# tri_to_ramp-pls_2-25-23.net
KiCad netlist of a schematic drawn in EAGLE
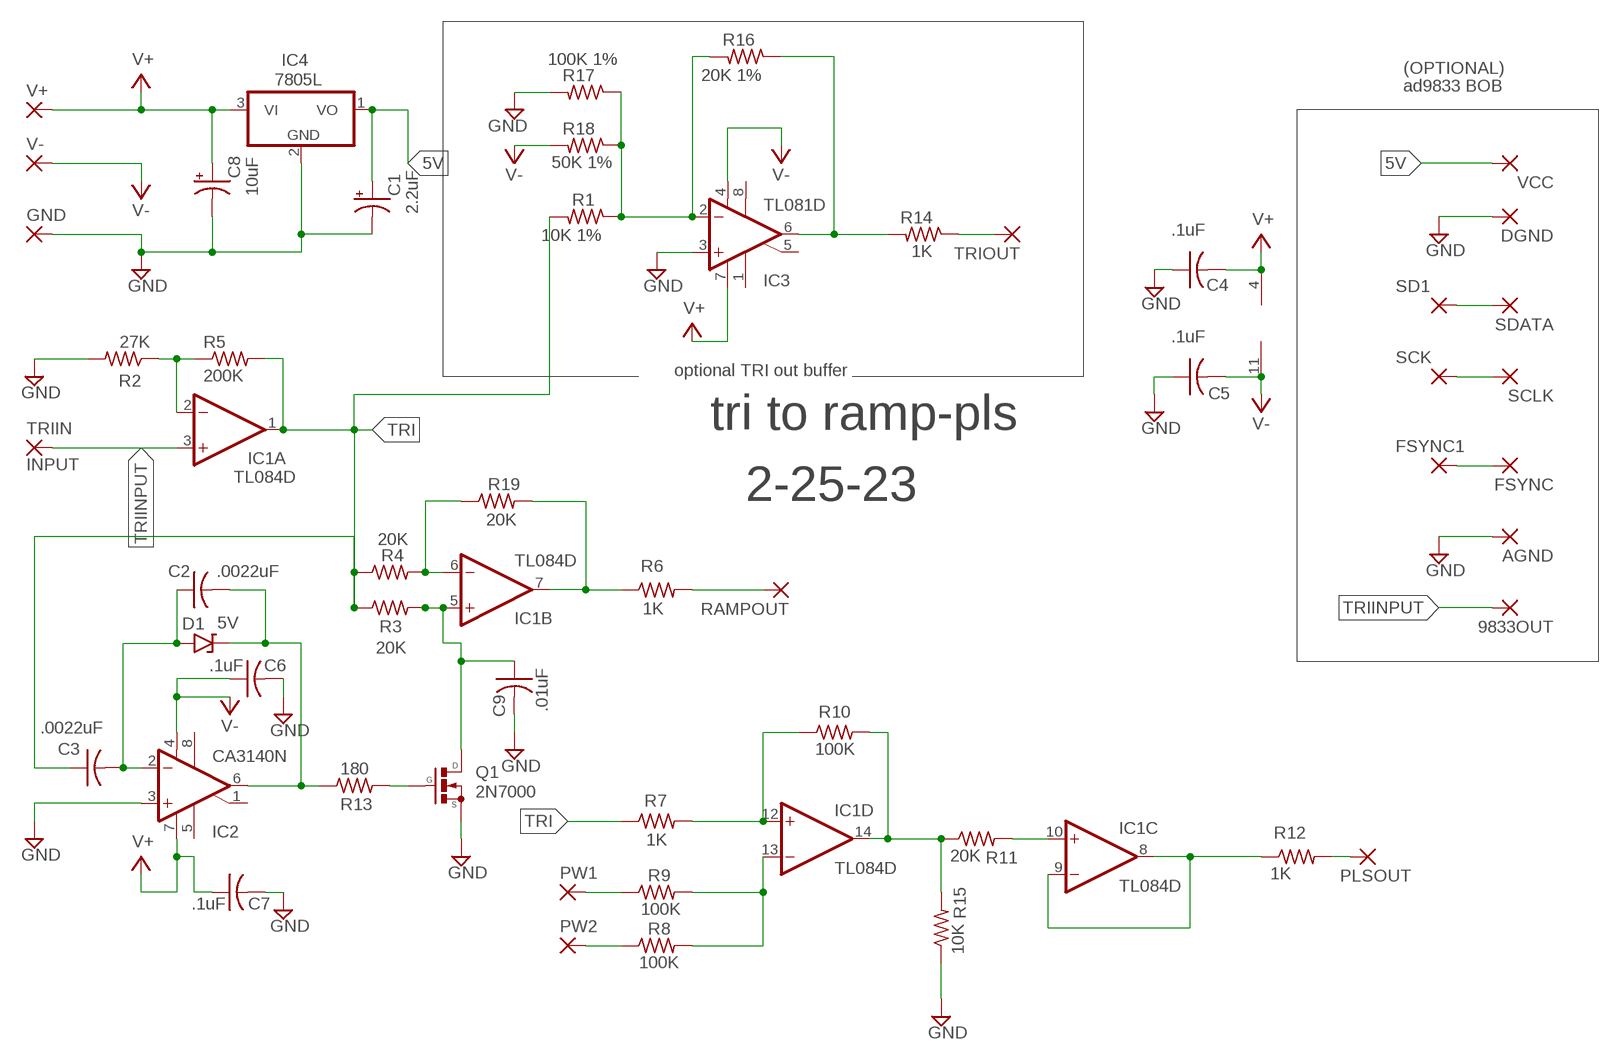
[diagram p0: schematic, sheet 1]

(export (version "E")
  (design (tool "Eeschema 10.0.6"))
  (components
    (comp (ref "9833OUT")
      (value "WIREPAD1,6/0,8")
      (footprint "eagle-import:1,6_0,8")
      (libsource (lib "eagle-import") (part "WIREPAD1,6/0,8"))
    )
    (comp (ref "AGND")
      (value "WIREPAD1,6/0,8")
      (footprint "eagle-import:1,6_0,8")
      (libsource (lib "eagle-import") (part "WIREPAD1,6/0,8"))
    )
    (comp (ref "C1")
      (value "2.2uF")
      (footprint "eagle-import:E5-4")
      (libsource (lib "eagle-import") (part "CPOL-USE5-4"))
    )
    (comp (ref "C2")
      (value ".0022uF")
      (footprint "eagle-import:C050-030X075")
      (libsource (lib "eagle-import") (part "C-US050-030X075"))
    )
    (comp (ref "C3")
      (value ".0022uF")
      (footprint "eagle-import:C050-035X075")
      (libsource (lib "eagle-import") (part "C-US050-035X075"))
    )
    (comp (ref "C4")
      (value ".1uF")
      (footprint "eagle-import:C025-025X050")
      (libsource (lib "eagle-import") (part "C-US025-025X050"))
    )
    (comp (ref "C5")
      (value ".1uF")
      (footprint "eagle-import:C025-025X050")
      (libsource (lib "eagle-import") (part "C-US025-025X050"))
    )
    (comp (ref "C6")
      (value ".1uF")
      (footprint "eagle-import:C025-025X050")
      (libsource (lib "eagle-import") (part "C-US025-025X050"))
    )
    (comp (ref "C7")
      (value ".1uF")
      (footprint "eagle-import:C025-025X050")
      (libsource (lib "eagle-import") (part "C-US025-025X050"))
    )
    (comp (ref "C8")
      (value "10uF")
      (footprint "eagle-import:E5-4")
      (libsource (lib "eagle-import") (part "CPOL-USE5-4"))
    )
    (comp (ref "C9")
      (value ".01uF")
      (footprint "eagle-import:C050-035X075")
      (libsource (lib "eagle-import") (part "C-US050-035X075"))
    )
    (comp (ref "D1")
      (value "5V")
      (footprint "eagle-import:DO41-3")
      (libsource (lib "eagle-import") (part "ZENER.3"))
    )
    (comp (ref "DGND")
      (value "WIREPAD1,6/0,8")
      (footprint "eagle-import:1,6_0,8")
      (libsource (lib "eagle-import") (part "WIREPAD1,6/0,8"))
    )
    (comp (ref "FSYNC")
      (value "WIREPAD1,6/0,8")
      (footprint "eagle-import:1,6_0,8")
      (libsource (lib "eagle-import") (part "WIREPAD1,6/0,8"))
    )
    (comp (ref "FSYNC1")
      (value "WIREPAD1,6/0,8")
      (footprint "eagle-import:1,6_0,8")
      (libsource (lib "eagle-import") (part "WIREPAD1,6/0,8"))
    )
    (comp (ref "GND")
      (value "WIREPAD1,6/0,8")
      (footprint "eagle-import:1,6_0,8")
      (libsource (lib "eagle-import") (part "WIREPAD1,6/0,8"))
    )
    (comp (ref "IC1")
      (value "TL084D")
      (footprint "eagle-import:SO14")
      (libsource (lib "eagle-import") (part "TL084D"))
    )
    (comp (ref "IC2")
      (value "CA3140N")
      (footprint "eagle-import:DIL08")
      (libsource (lib "eagle-import") (part "CA3140N"))
    )
    (comp (ref "IC3")
      (value "TL081D")
      (footprint "eagle-import:SO08")
      (libsource (lib "eagle-import") (part "TL081D"))
    )
    (comp (ref "IC4")
      (value "7805L")
      (footprint "eagle-import:ADAFRUIT_TO92")
      (libsource (lib "eagle-import") (part "ADAFRUIT_78L05"))
    )
    (comp (ref "PLSOUT")
      (value "WIREPAD1,6/0,8")
      (footprint "eagle-import:1,6_0,8")
      (libsource (lib "eagle-import") (part "WIREPAD1,6/0,8"))
    )
    (comp (ref "PW1")
      (value "WIREPAD1,6/0,8")
      (footprint "eagle-import:1,6_0,8")
      (libsource (lib "eagle-import") (part "WIREPAD1,6/0,8"))
    )
    (comp (ref "PW2")
      (value "WIREPAD1,6/0,8")
      (footprint "eagle-import:1,6_0,8")
      (libsource (lib "eagle-import") (part "WIREPAD1,6/0,8"))
    )
    (comp (ref "Q1")
      (value "2N7000")
      (footprint "eagle-import:TO92-")
      (libsource (lib "eagle-import") (part "2N7000"))
    )
    (comp (ref "R1")
      (value "10K 1%")
      (footprint "eagle-import:0204_7")
      (libsource (lib "eagle-import") (part "R-US_0204/7"))
    )
    (comp (ref "R2")
      (value "27K")
      (footprint "eagle-import:0204_7")
      (libsource (lib "eagle-import") (part "R-US_0204/7"))
    )
    (comp (ref "R3")
      (value "20K")
      (footprint "eagle-import:0204_7")
      (libsource (lib "eagle-import") (part "R-US_0204/7"))
    )
    (comp (ref "R4")
      (value "20K")
      (footprint "eagle-import:0204_7")
      (libsource (lib "eagle-import") (part "R-US_0204/7"))
    )
    (comp (ref "R5")
      (value "200K")
      (footprint "eagle-import:0204_7")
      (libsource (lib "eagle-import") (part "R-US_0204/7"))
    )
    (comp (ref "R6")
      (value "1K")
      (footprint "eagle-import:0204_7")
      (libsource (lib "eagle-import") (part "R-US_0204/7"))
    )
    (comp (ref "R7")
      (value "1K")
      (footprint "eagle-import:0204_7")
      (libsource (lib "eagle-import") (part "R-US_0204/7"))
    )
    (comp (ref "R8")
      (value "100K")
      (footprint "eagle-import:0204_7")
      (libsource (lib "eagle-import") (part "R-US_0204/7"))
    )
    (comp (ref "R9")
      (value "100K")
      (footprint "eagle-import:0204_7")
      (libsource (lib "eagle-import") (part "R-US_0204/7"))
    )
    (comp (ref "R10")
      (value "100K")
      (footprint "eagle-import:0204_7")
      (libsource (lib "eagle-import") (part "R-US_0204/7"))
    )
    (comp (ref "R11")
      (value "20K")
      (footprint "eagle-import:0204_7")
      (libsource (lib "eagle-import") (part "R-US_0204/7"))
    )
    (comp (ref "R12")
      (value "1K")
      (footprint "eagle-import:0204_7")
      (libsource (lib "eagle-import") (part "R-US_0204/7"))
    )
    (comp (ref "R13")
      (value "180")
      (footprint "eagle-import:0204_7")
      (libsource (lib "eagle-import") (part "R-US_0204/7"))
    )
    (comp (ref "R14")
      (value "1K")
      (footprint "eagle-import:0204_7")
      (libsource (lib "eagle-import") (part "R-US_0204/7"))
    )
    (comp (ref "R15")
      (value "10K")
      (footprint "eagle-import:0204_7")
      (libsource (lib "eagle-import") (part "R-US_0204/7"))
    )
    (comp (ref "R16")
      (value "20K 1%")
      (footprint "eagle-import:0204_7")
      (libsource (lib "eagle-import") (part "R-US_0204/7"))
    )
    (comp (ref "R17")
      (value "100K 1%")
      (footprint "eagle-import:0204_7")
      (libsource (lib "eagle-import") (part "R-US_0204/7"))
    )
    (comp (ref "R18")
      (value "50K 1%")
      (footprint "eagle-import:0204_7")
      (libsource (lib "eagle-import") (part "R-US_0204/7"))
    )
    (comp (ref "R19")
      (value "20K")
      (footprint "eagle-import:0204_7")
      (libsource (lib "eagle-import") (part "R-US_0204/7"))
    )
    (comp (ref "RAMPOUT")
      (value "WIREPAD1,6/0,8")
      (footprint "eagle-import:1,6_0,8")
      (libsource (lib "eagle-import") (part "WIREPAD1,6/0,8"))
    )
    (comp (ref "SCK")
      (value "WIREPAD1,6/0,8")
      (footprint "eagle-import:1,6_0,8")
      (libsource (lib "eagle-import") (part "WIREPAD1,6/0,8"))
    )
    (comp (ref "SCLK")
      (value "WIREPAD1,6/0,8")
      (footprint "eagle-import:1,6_0,8")
      (libsource (lib "eagle-import") (part "WIREPAD1,6/0,8"))
    )
    (comp (ref "SD1")
      (value "WIREPAD1,6/0,8")
      (footprint "eagle-import:1,6_0,8")
      (libsource (lib "eagle-import") (part "WIREPAD1,6/0,8"))
    )
    (comp (ref "SDATA")
      (value "WIREPAD1,6/0,8")
      (footprint "eagle-import:1,6_0,8")
      (libsource (lib "eagle-import") (part "WIREPAD1,6/0,8"))
    )
    (comp (ref "TRIIN")
      (value "INPUT")
      (footprint "eagle-import:1,6_0,8")
      (libsource (lib "eagle-import") (part "WIREPAD1,6/0,8"))
    )
    (comp (ref "TRIOUT")
      (value "WIREPAD1,6/0,8")
      (footprint "eagle-import:1,6_0,8")
      (libsource (lib "eagle-import") (part "WIREPAD1,6/0,8"))
    )
    (comp (ref "V+")
      (value "WIREPAD1,6/0,8")
      (footprint "eagle-import:1,6_0,8")
      (libsource (lib "eagle-import") (part "WIREPAD1,6/0,8"))
    )
    (comp (ref "V-")
      (value "WIREPAD1,6/0,8")
      (footprint "eagle-import:1,6_0,8")
      (libsource (lib "eagle-import") (part "WIREPAD1,6/0,8"))
    )
    (comp (ref "VCC")
      (value "WIREPAD1,6/0,8")
      (footprint "eagle-import:1,6_0,8")
      (libsource (lib "eagle-import") (part "WIREPAD1,6/0,8"))
    )
  )
  (nets
    (net (code "1") (name "5V") (class "Default")
      (node (ref "C1") (pin "+") (pinfunction "+_+") (pintype "passive"))
      (node (ref "IC4") (pin "1") (pinfunction "VO_1") (pintype "passive"))
      (node (ref "VCC") (pin "1") (pinfunction "P_1") (pintype "passive"))
    )
    (net (code "2") (name "GND") (class "Default")
      (node (ref "AGND") (pin "1") (pinfunction "P_1") (pintype "passive"))
      (node (ref "C1") (pin "-") (pinfunction "-_-") (pintype "passive"))
      (node (ref "C4") (pin "1") (pinfunction "1_1") (pintype "passive"))
      (node (ref "C5") (pin "1") (pinfunction "1_1") (pintype "passive"))
      (node (ref "C6") (pin "2") (pinfunction "2_2") (pintype "passive"))
      (node (ref "C7") (pin "2") (pinfunction "2_2") (pintype "passive"))
      (node (ref "C8") (pin "-") (pinfunction "-_-") (pintype "passive"))
      (node (ref "C9") (pin "2") (pinfunction "2_2") (pintype "passive"))
      (node (ref "DGND") (pin "1") (pinfunction "P_1") (pintype "passive"))
      (node (ref "GND") (pin "1") (pinfunction "P_1") (pintype "passive"))
      (node (ref "IC2") (pin "3") (pinfunction "+IN_3") (pintype "input"))
      (node (ref "IC3") (pin "3") (pinfunction "+IN_3") (pintype "input"))
      (node (ref "IC4") (pin "2") (pinfunction "GND_2") (pintype "passive"))
      (node (ref "Q1") (pin "3") (pinfunction "S_3") (pintype "passive"))
      (node (ref "R15") (pin "1") (pinfunction "1_1") (pintype "passive"))
      (node (ref "R17") (pin "2") (pinfunction "2_2") (pintype "passive"))
      (node (ref "R2") (pin "2") (pinfunction "2_2") (pintype "passive"))
    )
    (net (code "3") (name "Net-(FSYNC-P)") (class "Default")
      (node (ref "FSYNC") (pin "1") (pinfunction "P_1") (pintype "passive"))
      (node (ref "FSYNC1") (pin "1") (pinfunction "P_1") (pintype "passive"))
    )
    (net (code "4") (name "Net-(IC1A--IN)") (class "Default")
      (node (ref "IC1") (pin "2") (pinfunction "-IN_2") (pintype "input"))
      (node (ref "R2") (pin "1") (pinfunction "1_1") (pintype "passive"))
      (node (ref "R5") (pin "1") (pinfunction "1_1") (pintype "passive"))
    )
    (net (code "5") (name "Net-(IC1B-+IN)") (class "Default")
      (node (ref "C9") (pin "1") (pinfunction "1_1") (pintype "passive"))
      (node (ref "IC1") (pin "5") (pinfunction "+IN_5") (pintype "input"))
      (node (ref "Q1") (pin "1") (pinfunction "D_1") (pintype "passive"))
      (node (ref "R3") (pin "2") (pinfunction "2_2") (pintype "passive"))
    )
    (net (code "6") (name "Net-(IC1B--IN)") (class "Default")
      (node (ref "IC1") (pin "6") (pinfunction "-IN_6") (pintype "input"))
      (node (ref "R19") (pin "1") (pinfunction "1_1") (pintype "passive"))
      (node (ref "R4") (pin "2") (pinfunction "2_2") (pintype "passive"))
    )
    (net (code "7") (name "Net-(IC1B-OUT)") (class "Default")
      (node (ref "IC1") (pin "7") (pinfunction "OUT_7") (pintype "output"))
      (node (ref "R19") (pin "2") (pinfunction "2_2") (pintype "passive"))
      (node (ref "R6") (pin "1") (pinfunction "1_1") (pintype "passive"))
    )
    (net (code "8") (name "Net-(IC1C-+IN)") (class "Default")
      (node (ref "IC1") (pin "10") (pinfunction "+IN_10") (pintype "input"))
      (node (ref "R11") (pin "2") (pinfunction "2_2") (pintype "passive"))
    )
    (net (code "9") (name "Net-(IC1C--IN)") (class "Default")
      (node (ref "IC1") (pin "8") (pinfunction "OUT_8") (pintype "output"))
      (node (ref "IC1") (pin "9") (pinfunction "-IN_9") (pintype "input"))
      (node (ref "R12") (pin "1") (pinfunction "1_1") (pintype "passive"))
    )
    (net (code "10") (name "Net-(IC1D-+IN)") (class "Default")
      (node (ref "IC1") (pin "12") (pinfunction "+IN_12") (pintype "input"))
      (node (ref "R10") (pin "1") (pinfunction "1_1") (pintype "passive"))
      (node (ref "R7") (pin "2") (pinfunction "2_2") (pintype "passive"))
    )
    (net (code "11") (name "Net-(IC1D--IN)") (class "Default")
      (node (ref "IC1") (pin "13") (pinfunction "-IN_13") (pintype "input"))
      (node (ref "R8") (pin "2") (pinfunction "2_2") (pintype "passive"))
      (node (ref "R9") (pin "2") (pinfunction "2_2") (pintype "passive"))
    )
    (net (code "12") (name "Net-(IC1D-OUT)") (class "Default")
      (node (ref "IC1") (pin "14") (pinfunction "OUT_14") (pintype "output"))
      (node (ref "R10") (pin "2") (pinfunction "2_2") (pintype "passive"))
      (node (ref "R11") (pin "1") (pinfunction "1_1") (pintype "passive"))
      (node (ref "R15") (pin "2") (pinfunction "2_2") (pintype "passive"))
    )
    (net (code "13") (name "Net-(IC2--IN)") (class "Default")
      (node (ref "C2") (pin "1") (pinfunction "1_1") (pintype "passive"))
      (node (ref "C3") (pin "2") (pinfunction "2_2") (pintype "passive"))
      (node (ref "D1") (pin "A") (pinfunction "A_A") (pintype "passive"))
      (node (ref "IC2") (pin "2") (pinfunction "-IN_2") (pintype "input"))
    )
    (net (code "14") (name "Net-(IC2-OUT)") (class "Default")
      (node (ref "C2") (pin "2") (pinfunction "2_2") (pintype "passive"))
      (node (ref "D1") (pin "C") (pinfunction "C_C") (pintype "passive"))
      (node (ref "IC2") (pin "6") (pinfunction "OUT_6") (pintype "output"))
      (node (ref "R13") (pin "1") (pinfunction "1_1") (pintype "passive"))
    )
    (net (code "15") (name "Net-(IC3--IN)") (class "Default")
      (node (ref "IC3") (pin "2") (pinfunction "-IN_2") (pintype "input"))
      (node (ref "R1") (pin "1") (pinfunction "1_1") (pintype "passive"))
      (node (ref "R16") (pin "2") (pinfunction "2_2") (pintype "passive"))
      (node (ref "R17") (pin "1") (pinfunction "1_1") (pintype "passive"))
      (node (ref "R18") (pin "1") (pinfunction "1_1") (pintype "passive"))
    )
    (net (code "16") (name "Net-(IC3-OUT)") (class "Default")
      (node (ref "IC3") (pin "6") (pinfunction "OUT_6") (pintype "output"))
      (node (ref "R14") (pin "2") (pinfunction "2_2") (pintype "passive"))
      (node (ref "R16") (pin "1") (pinfunction "1_1") (pintype "passive"))
    )
    (net (code "17") (name "Net-(PLSOUT-P)") (class "Default")
      (node (ref "PLSOUT") (pin "1") (pinfunction "P_1") (pintype "passive"))
      (node (ref "R12") (pin "2") (pinfunction "2_2") (pintype "passive"))
    )
    (net (code "18") (name "Net-(PW1-P)") (class "Default")
      (node (ref "PW1") (pin "1") (pinfunction "P_1") (pintype "passive"))
      (node (ref "R9") (pin "1") (pinfunction "1_1") (pintype "passive"))
    )
    (net (code "19") (name "Net-(PW2-P)") (class "Default")
      (node (ref "PW2") (pin "1") (pinfunction "P_1") (pintype "passive"))
      (node (ref "R8") (pin "1") (pinfunction "1_1") (pintype "passive"))
    )
    (net (code "20") (name "Net-(Q1-G)") (class "Default")
      (node (ref "Q1") (pin "2") (pinfunction "G_2") (pintype "passive"))
      (node (ref "R13") (pin "2") (pinfunction "2_2") (pintype "passive"))
    )
    (net (code "21") (name "Net-(RAMPOUT-P)") (class "Default")
      (node (ref "R6") (pin "2") (pinfunction "2_2") (pintype "passive"))
      (node (ref "RAMPOUT") (pin "1") (pinfunction "P_1") (pintype "passive"))
    )
    (net (code "22") (name "Net-(SCK-P)") (class "Default")
      (node (ref "SCK") (pin "1") (pinfunction "P_1") (pintype "passive"))
      (node (ref "SCLK") (pin "1") (pinfunction "P_1") (pintype "passive"))
    )
    (net (code "23") (name "Net-(SD1-P)") (class "Default")
      (node (ref "SD1") (pin "1") (pinfunction "P_1") (pintype "passive"))
      (node (ref "SDATA") (pin "1") (pinfunction "P_1") (pintype "passive"))
    )
    (net (code "24") (name "Net-(TRIOUT-P)") (class "Default")
      (node (ref "R14") (pin "1") (pinfunction "1_1") (pintype "passive"))
      (node (ref "TRIOUT") (pin "1") (pinfunction "P_1") (pintype "passive"))
    )
    (net (code "25") (name "TRI") (class "Default")
      (node (ref "C3") (pin "1") (pinfunction "1_1") (pintype "passive"))
      (node (ref "IC1") (pin "1") (pinfunction "OUT_1") (pintype "output"))
      (node (ref "R1") (pin "2") (pinfunction "2_2") (pintype "passive"))
      (node (ref "R3") (pin "1") (pinfunction "1_1") (pintype "passive"))
      (node (ref "R4") (pin "1") (pinfunction "1_1") (pintype "passive"))
      (node (ref "R5") (pin "2") (pinfunction "2_2") (pintype "passive"))
      (node (ref "R7") (pin "1") (pinfunction "1_1") (pintype "passive"))
    )
    (net (code "26") (name "TRIINPUT") (class "Default")
      (node (ref "9833OUT") (pin "1") (pinfunction "P_1") (pintype "passive"))
      (node (ref "IC1") (pin "3") (pinfunction "+IN_3") (pintype "input"))
      (node (ref "TRIIN") (pin "1") (pinfunction "P_1") (pintype "passive"))
    )
    (net (code "27") (name "V+") (class "Default")
      (node (ref "C4") (pin "2") (pinfunction "2_2") (pintype "passive"))
      (node (ref "C7") (pin "1") (pinfunction "1_1") (pintype "passive"))
      (node (ref "C8") (pin "+") (pinfunction "+_+") (pintype "passive"))
      (node (ref "IC1") (pin "4") (pinfunction "V+_4") (pintype "power_in"))
      (node (ref "IC2") (pin "7") (pinfunction "V+_7") (pintype "power_in"))
      (node (ref "IC3") (pin "7") (pinfunction "V+_7") (pintype "power_in"))
      (node (ref "IC4") (pin "3") (pinfunction "VI_3") (pintype "input"))
      (node (ref "V+") (pin "1") (pinfunction "P_1") (pintype "passive"))
    )
    (net (code "28") (name "V-") (class "Default")
      (node (ref "C5") (pin "2") (pinfunction "2_2") (pintype "passive"))
      (node (ref "C6") (pin "1") (pinfunction "1_1") (pintype "passive"))
      (node (ref "IC1") (pin "11") (pinfunction "V-_11") (pintype "power_in"))
      (node (ref "IC2") (pin "4") (pinfunction "V-_4") (pintype "power_in"))
      (node (ref "IC3") (pin "4") (pinfunction "V-_4") (pintype "power_in"))
      (node (ref "R18") (pin "2") (pinfunction "2_2") (pintype "passive"))
      (node (ref "V-") (pin "1") (pinfunction "P_1") (pintype "passive"))
    )
    (net (code "29") (name "unconnected-(IC2-CMP-Pad8)") (class "Default")
      (node (ref "IC2") (pin "8") (pinfunction "CMP_8") (pintype "passive"))
    )
    (net (code "30") (name "unconnected-(IC2-ON-Pad5)") (class "Default")
      (node (ref "IC2") (pin "5") (pinfunction "ON_5") (pintype "passive"))
    )
    (net (code "31") (name "unconnected-(IC2-ON{slash}CMP-Pad1)") (class "Default")
      (node (ref "IC2") (pin "1") (pinfunction "ON/CMP_1") (pintype "passive"))
    )
    (net (code "32") (name "unconnected-(IC3-ON1-Pad1)") (class "Default")
      (node (ref "IC3") (pin "1") (pinfunction "ON1_1") (pintype "passive"))
    )
    (net (code "33") (name "unconnected-(IC3-ON2-Pad5)") (class "Default")
      (node (ref "IC3") (pin "5") (pinfunction "ON2_5") (pintype "passive"))
    )
    (net (code "34") (name "unconnected-(IC3-OPT-Pad8)") (class "Default")
      (node (ref "IC3") (pin "8") (pinfunction "OPT_8") (pintype "passive"))
    )
  )
)
